# FrontendModulev2.net
KiCad netlist of a schematic drawn in EAGLE
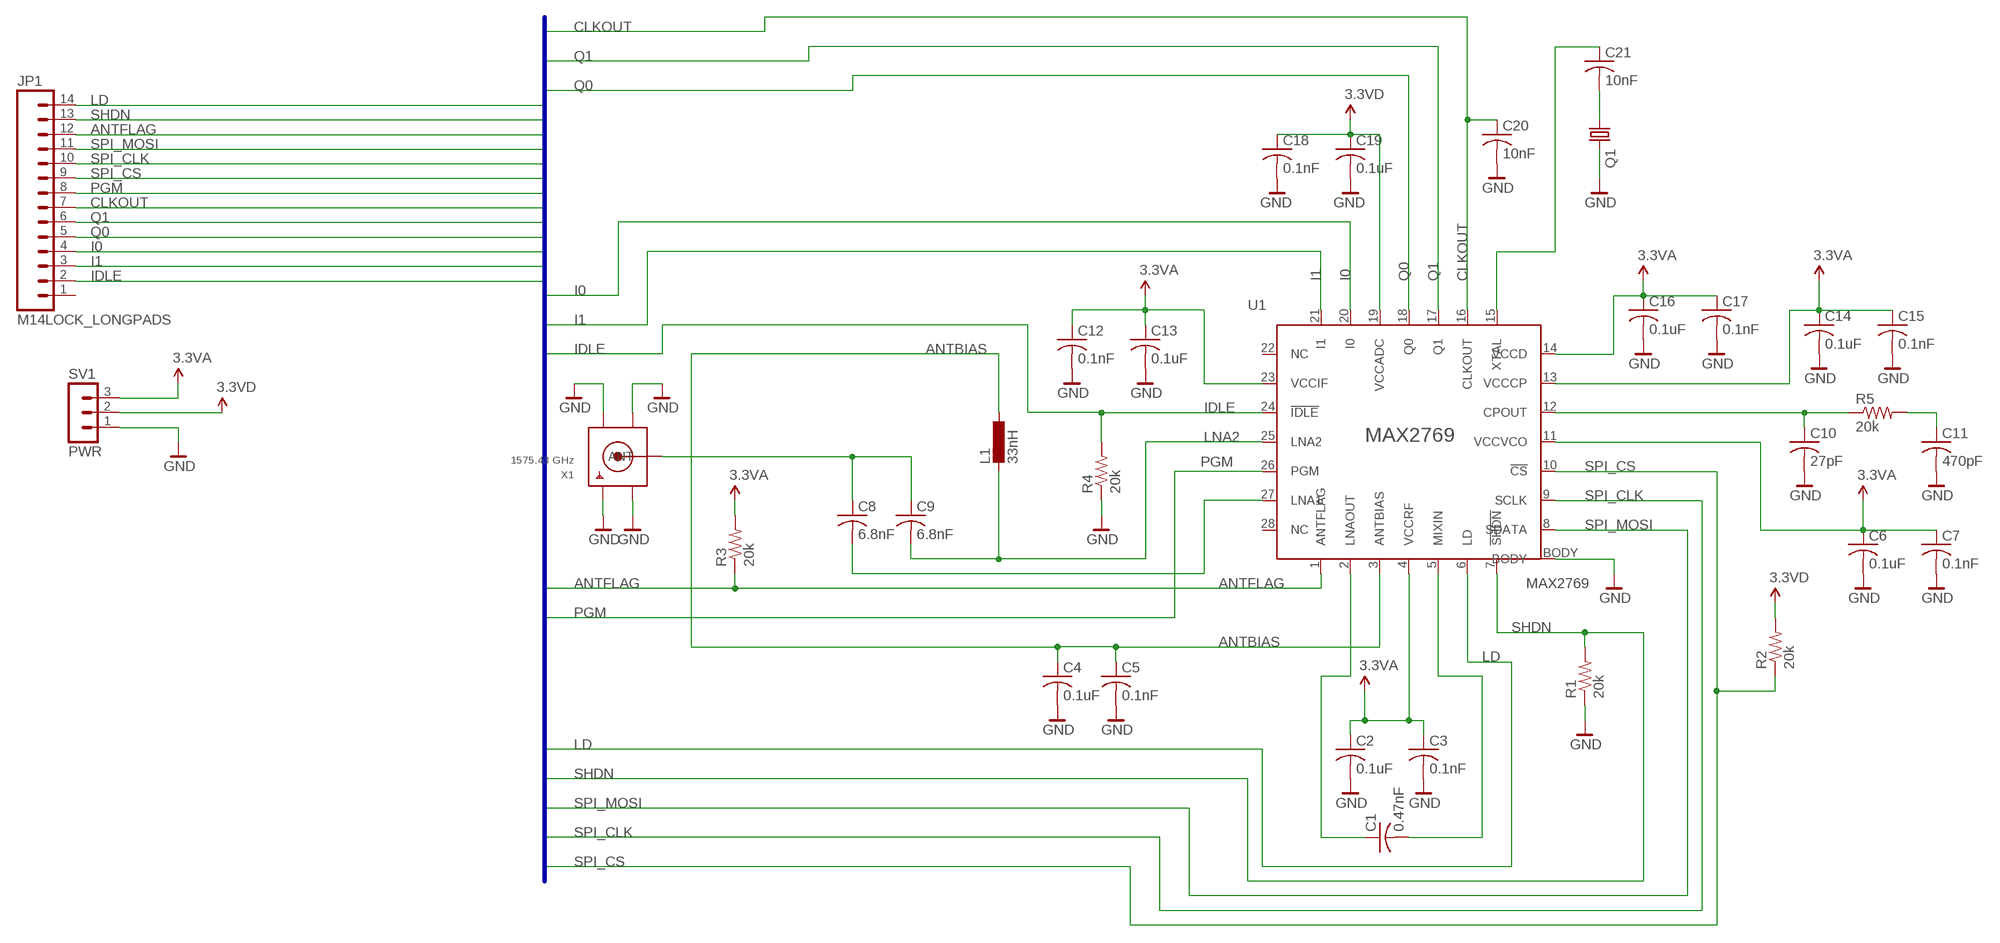
[diagram p0: schematic, sheet 1]

(export (version "E")
  (design (tool "Eeschema 10.0.6"))
  (components
    (comp (ref "C1")
      (value "0.47nF")
      (footprint "eagle-import:C0805K")
      (libsource (lib "eagle-import") (part "C-USC0805K"))
    )
    (comp (ref "C2")
      (value "0.1uF")
      (footprint "eagle-import:C0805K")
      (libsource (lib "eagle-import") (part "C-USC0805K"))
    )
    (comp (ref "C3")
      (value "0.1nF")
      (footprint "eagle-import:C0805K")
      (libsource (lib "eagle-import") (part "C-USC0805K"))
    )
    (comp (ref "C4")
      (value "0.1uF")
      (footprint "eagle-import:C0805K")
      (libsource (lib "eagle-import") (part "C-USC0805K"))
    )
    (comp (ref "C5")
      (value "0.1nF")
      (footprint "eagle-import:C0805K")
      (libsource (lib "eagle-import") (part "C-USC0805K"))
    )
    (comp (ref "C6")
      (value "0.1uF")
      (footprint "eagle-import:C0805K")
      (libsource (lib "eagle-import") (part "C-USC0805K"))
    )
    (comp (ref "C7")
      (value "0.1nF")
      (footprint "eagle-import:C0805K")
      (libsource (lib "eagle-import") (part "C-USC0805K"))
    )
    (comp (ref "C8")
      (value "6.8nF")
      (footprint "eagle-import:C0805K")
      (libsource (lib "eagle-import") (part "C-USC0805K"))
    )
    (comp (ref "C9")
      (value "6.8nF")
      (footprint "eagle-import:C0805K")
      (libsource (lib "eagle-import") (part "C-USC0805K"))
    )
    (comp (ref "C10")
      (value "27pF")
      (footprint "eagle-import:C0805K")
      (libsource (lib "eagle-import") (part "C-USC0805K"))
    )
    (comp (ref "C11")
      (value "470pF")
      (footprint "eagle-import:C0805K")
      (libsource (lib "eagle-import") (part "C-USC0805K"))
    )
    (comp (ref "C12")
      (value "0.1nF")
      (footprint "eagle-import:C0805K")
      (libsource (lib "eagle-import") (part "C-USC0805K"))
    )
    (comp (ref "C13")
      (value "0.1uF")
      (footprint "eagle-import:C0805K")
      (libsource (lib "eagle-import") (part "C-USC0805K"))
    )
    (comp (ref "C14")
      (value "0.1uF")
      (footprint "eagle-import:C0805K")
      (libsource (lib "eagle-import") (part "C-USC0805K"))
    )
    (comp (ref "C15")
      (value "0.1nF")
      (footprint "eagle-import:C0805K")
      (libsource (lib "eagle-import") (part "C-USC0805K"))
    )
    (comp (ref "C16")
      (value "0.1uF")
      (footprint "eagle-import:C0805K")
      (libsource (lib "eagle-import") (part "C-USC0805K"))
    )
    (comp (ref "C17")
      (value "0.1nF")
      (footprint "eagle-import:C0805K")
      (libsource (lib "eagle-import") (part "C-USC0805K"))
    )
    (comp (ref "C18")
      (value "0.1nF")
      (footprint "eagle-import:C0805K")
      (libsource (lib "eagle-import") (part "C-USC0805K"))
    )
    (comp (ref "C19")
      (value "0.1uF")
      (footprint "eagle-import:C0805K")
      (libsource (lib "eagle-import") (part "C-USC0805K"))
    )
    (comp (ref "C20")
      (value "10nF")
      (footprint "eagle-import:C0805K")
      (libsource (lib "eagle-import") (part "C-USC0805K"))
    )
    (comp (ref "C21")
      (value "10nF")
      (footprint "eagle-import:C0805K")
      (libsource (lib "eagle-import") (part "C-USC0805K"))
    )
    (comp (ref "JP1")
      (value "M14LOCK_LONGPADS")
      (footprint "eagle-import:1X14_LOCK_LONGPADS")
      (libsource (lib "eagle-import") (part "M14LOCK_LONGPADS"))
    )
    (comp (ref "L1")
      (value "33nH")
      (footprint "eagle-import:L2012C")
      (libsource (lib "eagle-import") (part "L-EUL2012C"))
    )
    (comp (ref "Q1")
      (value "CRYSTALCTS406")
      (footprint "eagle-import:CTS406")
      (libsource (lib "eagle-import") (part "CRYSTALCTS406"))
    )
    (comp (ref "R1")
      (value "20k")
      (footprint "eagle-import:R0805")
      (libsource (lib "eagle-import") (part "R-US_R0805"))
    )
    (comp (ref "R2")
      (value "20k")
      (footprint "eagle-import:R0805")
      (libsource (lib "eagle-import") (part "R-US_R0805"))
    )
    (comp (ref "R3")
      (value "20k")
      (footprint "eagle-import:R0805")
      (libsource (lib "eagle-import") (part "R-US_R0805"))
    )
    (comp (ref "R4")
      (value "20k")
      (footprint "eagle-import:R0805")
      (libsource (lib "eagle-import") (part "R-US_R0805"))
    )
    (comp (ref "R5")
      (value "20k")
      (footprint "eagle-import:R0805")
      (libsource (lib "eagle-import") (part "R-US_R0805"))
    )
    (comp (ref "SV1")
      (value "PWR")
      (footprint "eagle-import:MA03-1")
      (libsource (lib "eagle-import") (part "MA03-1"))
    )
    (comp (ref "U1")
      (value "MAX2769")
      (footprint "eagle-import:90-0023")
      (libsource (lib "eagle-import") (part "MAX2769"))
    )
    (comp (ref "X1")
      (value "1575.43 GHz")
      (footprint "eagle-import:SMA90_DIP")
      (libsource (lib "eagle-import") (part "SMACONNECTOR"))
    )
  )
  (nets
    (net (code "1") (name "/ANTBIAS") (class "Default")
      (node (ref "C4") (pin "1") (pinfunction "1_1") (pintype "passive"))
      (node (ref "C5") (pin "1") (pinfunction "1_1") (pintype "passive"))
      (node (ref "L1") (pin "1") (pinfunction "1_1") (pintype "passive"))
      (node (ref "U1") (pin "3") (pinfunction "ANTBIAS_3") (pintype "output"))
    )
    (net (code "2") (name "/ANTFLAG") (class "Default")
      (node (ref "JP1") (pin "12") (pinfunction "12_12") (pintype "passive"))
      (node (ref "R3") (pin "1") (pinfunction "1_1") (pintype "passive"))
      (node (ref "U1") (pin "1") (pinfunction "ANTFLAG_1") (pintype "output"))
    )
    (net (code "3") (name "/CLKOUT") (class "Default")
      (node (ref "C20") (pin "1") (pinfunction "1_1") (pintype "passive"))
      (node (ref "JP1") (pin "7") (pinfunction "7_7") (pintype "passive"))
      (node (ref "U1") (pin "16") (pinfunction "CLKOUT_16") (pintype "output"))
    )
    (net (code "4") (name "/I0") (class "Default")
      (node (ref "JP1") (pin "4") (pinfunction "4_4") (pintype "passive"))
      (node (ref "U1") (pin "20") (pinfunction "I0_20") (pintype "output"))
    )
    (net (code "5") (name "/I1") (class "Default")
      (node (ref "JP1") (pin "3") (pinfunction "3_3") (pintype "passive"))
      (node (ref "U1") (pin "21") (pinfunction "I1_21") (pintype "output"))
    )
    (net (code "6") (name "/IDLE") (class "Default")
      (node (ref "JP1") (pin "2") (pinfunction "2_2") (pintype "passive"))
      (node (ref "R4") (pin "2") (pinfunction "2_2") (pintype "passive"))
      (node (ref "U1") (pin "24") (pinfunction "~{IDLE}_24") (pintype "input"))
    )
    (net (code "7") (name "/LD") (class "Default")
      (node (ref "JP1") (pin "14") (pinfunction "14_14") (pintype "passive"))
      (node (ref "U1") (pin "6") (pinfunction "LD_6") (pintype "output"))
    )
    (net (code "8") (name "/LNA2") (class "Default")
      (node (ref "C9") (pin "2") (pinfunction "2_2") (pintype "passive"))
      (node (ref "L1") (pin "2") (pinfunction "2_2") (pintype "passive"))
      (node (ref "U1") (pin "25") (pinfunction "LNA2_25") (pintype "passive"))
    )
    (net (code "9") (name "/PGM") (class "Default")
      (node (ref "JP1") (pin "8") (pinfunction "8_8") (pintype "passive"))
      (node (ref "U1") (pin "26") (pinfunction "PGM_26") (pintype "input"))
    )
    (net (code "10") (name "/Q0") (class "Default")
      (node (ref "JP1") (pin "5") (pinfunction "5_5") (pintype "passive"))
      (node (ref "U1") (pin "18") (pinfunction "Q0_18") (pintype "output"))
    )
    (net (code "11") (name "/Q1") (class "Default")
      (node (ref "JP1") (pin "6") (pinfunction "6_6") (pintype "passive"))
      (node (ref "U1") (pin "17") (pinfunction "Q1_17") (pintype "output"))
    )
    (net (code "12") (name "/SHDN") (class "Default")
      (node (ref "JP1") (pin "13") (pinfunction "13_13") (pintype "passive"))
      (node (ref "R1") (pin "2") (pinfunction "2_2") (pintype "passive"))
      (node (ref "U1") (pin "7") (pinfunction "~{SHDN}_7") (pintype "input"))
    )
    (net (code "13") (name "/SPI_CLK") (class "Default")
      (node (ref "JP1") (pin "10") (pinfunction "10_10") (pintype "passive"))
      (node (ref "U1") (pin "9") (pinfunction "SCLK_9") (pintype "input"))
    )
    (net (code "14") (name "/SPI_CS") (class "Default")
      (node (ref "JP1") (pin "9") (pinfunction "9_9") (pintype "passive"))
      (node (ref "R2") (pin "1") (pinfunction "1_1") (pintype "passive"))
      (node (ref "U1") (pin "10") (pinfunction "~{CS}_10") (pintype "input"))
    )
    (net (code "15") (name "/SPI_MOSI") (class "Default")
      (node (ref "JP1") (pin "11") (pinfunction "11_11") (pintype "passive"))
      (node (ref "U1") (pin "8") (pinfunction "SDATA_8") (pintype "bidirectional"))
    )
    (net (code "16") (name "3.3VA") (class "Default")
      (node (ref "C12") (pin "1") (pinfunction "1_1") (pintype "passive"))
      (node (ref "C13") (pin "1") (pinfunction "1_1") (pintype "passive"))
      (node (ref "C14") (pin "1") (pinfunction "1_1") (pintype "passive"))
      (node (ref "C15") (pin "1") (pinfunction "1_1") (pintype "passive"))
      (node (ref "C16") (pin "1") (pinfunction "1_1") (pintype "passive"))
      (node (ref "C17") (pin "1") (pinfunction "1_1") (pintype "passive"))
      (node (ref "C2") (pin "1") (pinfunction "1_1") (pintype "passive"))
      (node (ref "C3") (pin "1") (pinfunction "1_1") (pintype "passive"))
      (node (ref "C6") (pin "1") (pinfunction "1_1") (pintype "passive"))
      (node (ref "C7") (pin "1") (pinfunction "1_1") (pintype "passive"))
      (node (ref "R3") (pin "2") (pinfunction "2_2") (pintype "passive"))
      (node (ref "SV1") (pin "3") (pinfunction "3_3") (pintype "passive"))
      (node (ref "U1") (pin "11") (pinfunction "VCCVCO_11") (pintype "power_in"))
      (node (ref "U1") (pin "13") (pinfunction "VCCCP_13") (pintype "power_in"))
      (node (ref "U1") (pin "14") (pinfunction "VCCD_14") (pintype "power_in"))
      (node (ref "U1") (pin "23") (pinfunction "VCCIF_23") (pintype "power_in"))
      (node (ref "U1") (pin "4") (pinfunction "VCCRF_4") (pintype "power_in"))
    )
    (net (code "17") (name "3.3VD") (class "Default")
      (node (ref "C18") (pin "1") (pinfunction "1_1") (pintype "passive"))
      (node (ref "C19") (pin "1") (pinfunction "1_1") (pintype "passive"))
      (node (ref "R2") (pin "2") (pinfunction "2_2") (pintype "passive"))
      (node (ref "SV1") (pin "2") (pinfunction "2_2") (pintype "passive"))
      (node (ref "U1") (pin "19") (pinfunction "VCCADC_19") (pintype "power_in"))
    )
    (net (code "18") (name "GND") (class "Default")
      (node (ref "C10") (pin "2") (pinfunction "2_2") (pintype "passive"))
      (node (ref "C11") (pin "2") (pinfunction "2_2") (pintype "passive"))
      (node (ref "C12") (pin "2") (pinfunction "2_2") (pintype "passive"))
      (node (ref "C13") (pin "2") (pinfunction "2_2") (pintype "passive"))
      (node (ref "C14") (pin "2") (pinfunction "2_2") (pintype "passive"))
      (node (ref "C15") (pin "2") (pinfunction "2_2") (pintype "passive"))
      (node (ref "C16") (pin "2") (pinfunction "2_2") (pintype "passive"))
      (node (ref "C17") (pin "2") (pinfunction "2_2") (pintype "passive"))
      (node (ref "C18") (pin "2") (pinfunction "2_2") (pintype "passive"))
      (node (ref "C19") (pin "2") (pinfunction "2_2") (pintype "passive"))
      (node (ref "C2") (pin "2") (pinfunction "2_2") (pintype "passive"))
      (node (ref "C20") (pin "2") (pinfunction "2_2") (pintype "passive"))
      (node (ref "C3") (pin "2") (pinfunction "2_2") (pintype "passive"))
      (node (ref "C4") (pin "2") (pinfunction "2_2") (pintype "passive"))
      (node (ref "C5") (pin "2") (pinfunction "2_2") (pintype "passive"))
      (node (ref "C6") (pin "2") (pinfunction "2_2") (pintype "passive"))
      (node (ref "C7") (pin "2") (pinfunction "2_2") (pintype "passive"))
      (node (ref "Q1") (pin "3") (pinfunction "2_3") (pintype "passive"))
      (node (ref "R1") (pin "1") (pinfunction "1_1") (pintype "passive"))
      (node (ref "R4") (pin "1") (pinfunction "1_1") (pintype "passive"))
      (node (ref "SV1") (pin "1") (pinfunction "1_1") (pintype "passive"))
      (node (ref "U1") (pin "BODY") (pinfunction "BODY_BODY") (pintype "power_in"))
      (node (ref "X1") (pin "GND1") (pinfunction "GND1_GND1") (pintype "power_in"))
      (node (ref "X1") (pin "GND2") (pinfunction "GND2_GND2") (pintype "power_in"))
      (node (ref "X1") (pin "GND3") (pinfunction "GND3_GND3") (pintype "power_in"))
      (node (ref "X1") (pin "GND4") (pinfunction "GND4_GND4") (pintype "power_in"))
    )
    (net (code "19") (name "Net-(C11-Pad1)") (class "Default")
      (node (ref "C11") (pin "1") (pinfunction "1_1") (pintype "passive"))
      (node (ref "R5") (pin "2") (pinfunction "2_2") (pintype "passive"))
    )
    (net (code "20") (name "Net-(C21-Pad2)") (class "Default")
      (node (ref "C21") (pin "2") (pinfunction "2_2") (pintype "passive"))
      (node (ref "Q1") (pin "1") (pinfunction "1_1") (pintype "passive"))
    )
    (net (code "21") (name "Net-(U1-CPOUT)") (class "Default")
      (node (ref "C10") (pin "1") (pinfunction "1_1") (pintype "passive"))
      (node (ref "R5") (pin "1") (pinfunction "1_1") (pintype "passive"))
      (node (ref "U1") (pin "12") (pinfunction "CPOUT_12") (pintype "passive"))
    )
    (net (code "22") (name "Net-(U1-LNA1)") (class "Default")
      (node (ref "C8") (pin "2") (pinfunction "2_2") (pintype "passive"))
      (node (ref "U1") (pin "27") (pinfunction "LNA1_27") (pintype "passive"))
    )
    (net (code "23") (name "Net-(U1-LNAOUT)") (class "Default")
      (node (ref "C1") (pin "1") (pinfunction "1_1") (pintype "passive"))
      (node (ref "U1") (pin "2") (pinfunction "LNAOUT_2") (pintype "passive"))
    )
    (net (code "24") (name "Net-(U1-MIXIN)") (class "Default")
      (node (ref "C1") (pin "2") (pinfunction "2_2") (pintype "passive"))
      (node (ref "U1") (pin "5") (pinfunction "MIXIN_5") (pintype "passive"))
    )
    (net (code "25") (name "Net-(U1-XTAL)") (class "Default")
      (node (ref "C21") (pin "1") (pinfunction "1_1") (pintype "passive"))
      (node (ref "U1") (pin "15") (pinfunction "XTAL_15") (pintype "input"))
    )
    (net (code "26") (name "Net-(X1-ANT)") (class "Default")
      (node (ref "C8") (pin "1") (pinfunction "1_1") (pintype "passive"))
      (node (ref "C9") (pin "1") (pinfunction "1_1") (pintype "passive"))
      (node (ref "X1") (pin "ANTENNA") (pinfunction "ANT_ANTENNA") (pintype "bidirectional"))
    )
    (net (code "27") (name "unconnected-(JP1-Pad1)") (class "Default")
      (node (ref "JP1") (pin "1") (pinfunction "1_1") (pintype "passive"))
    )
    (net (code "28") (name "unconnected-(U1-NC-Pad22)") (class "Default")
      (node (ref "U1") (pin "22") (pinfunction "NC_22") (pintype "no_connect"))
    )
    (net (code "29") (name "unconnected-(U1-NC-Pad28)") (class "Default")
      (node (ref "U1") (pin "28") (pinfunction "NC_28") (pintype "no_connect"))
    )
  )
)
